# Metvoc2_0.net
KiCad netlist of a schematic drawn in EAGLE
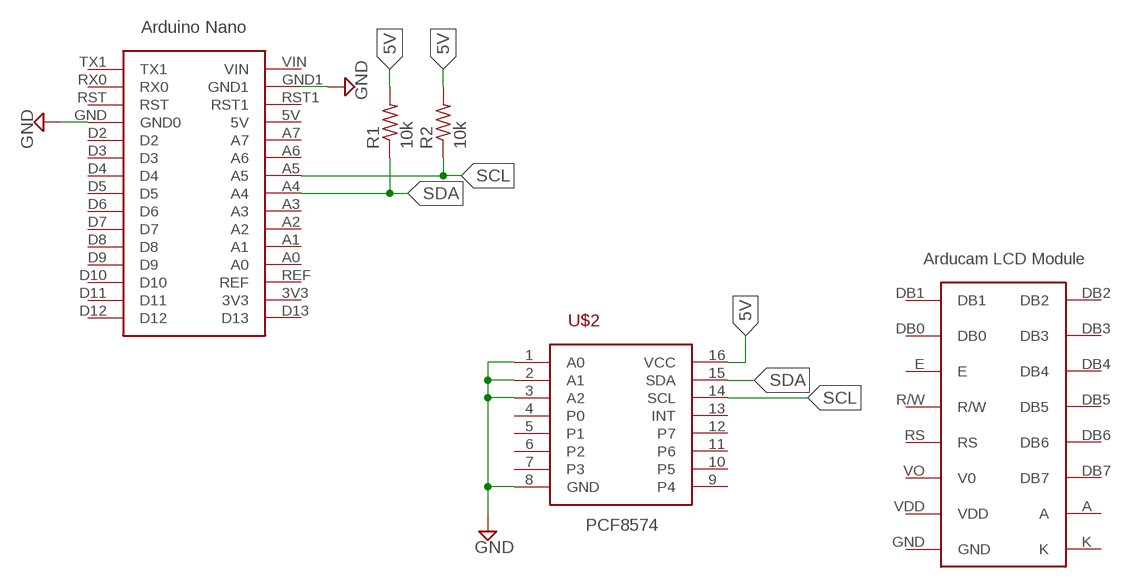
[diagram p0: schematic, sheet 1]

(export (version "E")
  (design (tool "Eeschema 10.0.6"))
  (components
    (comp (ref "R1")
      (value "10k")
      (footprint "eagle-import:M1206")
      (libsource (lib "eagle-import") (part "R-US_M1206"))
    )
    (comp (ref "R2")
      (value "10k")
      (footprint "eagle-import:M1206")
      (libsource (lib "eagle-import") (part "R-US_M1206"))
    )
    (comp (ref "U$1")
      (value "ARDUINO_NANO")
      (footprint "eagle-import:ARDUINONANO")
      (libsource (lib "eagle-import") (part "ARDUINO_NANO"))
    )
    (comp (ref "U$2")
      (value "PCF8574")
      (footprint "eagle-import:SO16")
      (libsource (lib "eagle-import") (part "PCF8574"))
    )
    (comp (ref "U$3")
      (value "LCDMODULE")
      (footprint "eagle-import:LCDSCREEN")
      (libsource (lib "eagle-import") (part "LCDMODULE"))
    )
  )
  (nets
    (net (code "1") (name "5V") (class "Default")
      (node (ref "R1") (pin "2") (pinfunction "2_2") (pintype "passive"))
      (node (ref "R2") (pin "2") (pinfunction "2_2") (pintype "passive"))
      (node (ref "U$2") (pin "16") (pinfunction "VCC_16") (pintype "bidirectional"))
    )
    (net (code "2") (name "GND") (class "Default")
      (node (ref "U$1") (pin "GND") (pinfunction "GND0_GND") (pintype "bidirectional"))
      (node (ref "U$1") (pin "GND1") (pinfunction "GND1_GND1") (pintype "bidirectional"))
      (node (ref "U$2") (pin "1") (pinfunction "A0_1") (pintype "bidirectional"))
      (node (ref "U$2") (pin "2") (pinfunction "A1_2") (pintype "bidirectional"))
      (node (ref "U$2") (pin "3") (pinfunction "A2_3") (pintype "bidirectional"))
      (node (ref "U$2") (pin "8") (pinfunction "GND_8") (pintype "bidirectional"))
    )
    (net (code "3") (name "SCL") (class "Default")
      (node (ref "R2") (pin "1") (pinfunction "1_1") (pintype "passive"))
      (node (ref "U$1") (pin "A5") (pinfunction "A5_A5") (pintype "bidirectional"))
      (node (ref "U$2") (pin "14") (pinfunction "SCL_14") (pintype "bidirectional"))
    )
    (net (code "4") (name "SDA") (class "Default")
      (node (ref "R1") (pin "1") (pinfunction "1_1") (pintype "passive"))
      (node (ref "U$1") (pin "A4") (pinfunction "A4_A4") (pintype "bidirectional"))
      (node (ref "U$2") (pin "15") (pinfunction "SDA_15") (pintype "bidirectional"))
    )
    (net (code "5") (name "unconnected-(U$1-Pad3V3)") (class "Default")
      (node (ref "U$1") (pin "3V3") (pinfunction "3V3_3V3") (pintype "bidirectional"))
    )
    (net (code "6") (name "unconnected-(U$1-Pad5V)") (class "Default")
      (node (ref "U$1") (pin "5V") (pinfunction "5V_5V") (pintype "bidirectional"))
    )
    (net (code "7") (name "unconnected-(U$1-PadA0)") (class "Default")
      (node (ref "U$1") (pin "A0") (pinfunction "A0_A0") (pintype "bidirectional"))
    )
    (net (code "8") (name "unconnected-(U$1-PadA1)") (class "Default")
      (node (ref "U$1") (pin "A1") (pinfunction "A1_A1") (pintype "bidirectional"))
    )
    (net (code "9") (name "unconnected-(U$1-PadA2)") (class "Default")
      (node (ref "U$1") (pin "A2") (pinfunction "A2_A2") (pintype "bidirectional"))
    )
    (net (code "10") (name "unconnected-(U$1-PadA3)") (class "Default")
      (node (ref "U$1") (pin "A3") (pinfunction "A3_A3") (pintype "bidirectional"))
    )
    (net (code "11") (name "unconnected-(U$1-PadA6)") (class "Default")
      (node (ref "U$1") (pin "A6") (pinfunction "A6_A6") (pintype "bidirectional"))
    )
    (net (code "12") (name "unconnected-(U$1-PadA7)") (class "Default")
      (node (ref "U$1") (pin "A7") (pinfunction "A7_A7") (pintype "bidirectional"))
    )
    (net (code "13") (name "unconnected-(U$1-PadD2)") (class "Default")
      (node (ref "U$1") (pin "D2") (pinfunction "D2_D2") (pintype "bidirectional"))
    )
    (net (code "14") (name "unconnected-(U$1-PadD3)") (class "Default")
      (node (ref "U$1") (pin "D3") (pinfunction "D3_D3") (pintype "bidirectional"))
    )
    (net (code "15") (name "unconnected-(U$1-PadD4)") (class "Default")
      (node (ref "U$1") (pin "D4") (pinfunction "D4_D4") (pintype "bidirectional"))
    )
    (net (code "16") (name "unconnected-(U$1-PadD5)") (class "Default")
      (node (ref "U$1") (pin "D5") (pinfunction "D5_D5") (pintype "bidirectional"))
    )
    (net (code "17") (name "unconnected-(U$1-PadD6)") (class "Default")
      (node (ref "U$1") (pin "D6") (pinfunction "D6_D6") (pintype "bidirectional"))
    )
    (net (code "18") (name "unconnected-(U$1-PadD7)") (class "Default")
      (node (ref "U$1") (pin "D7") (pinfunction "D7_D7") (pintype "bidirectional"))
    )
    (net (code "19") (name "unconnected-(U$1-PadD8)") (class "Default")
      (node (ref "U$1") (pin "D8") (pinfunction "D8_D8") (pintype "bidirectional"))
    )
    (net (code "20") (name "unconnected-(U$1-PadD9)") (class "Default")
      (node (ref "U$1") (pin "D9") (pinfunction "D9_D9") (pintype "bidirectional"))
    )
    (net (code "21") (name "unconnected-(U$1-PadD10)") (class "Default")
      (node (ref "U$1") (pin "D10") (pinfunction "D10_D10") (pintype "bidirectional"))
    )
    (net (code "22") (name "unconnected-(U$1-PadD11)") (class "Default")
      (node (ref "U$1") (pin "D11") (pinfunction "D11_D11") (pintype "bidirectional"))
    )
    (net (code "23") (name "unconnected-(U$1-PadD12)") (class "Default")
      (node (ref "U$1") (pin "D12") (pinfunction "D12_D12") (pintype "bidirectional"))
    )
    (net (code "24") (name "unconnected-(U$1-PadD13)") (class "Default")
      (node (ref "U$1") (pin "D13") (pinfunction "D13_D13") (pintype "bidirectional"))
    )
    (net (code "25") (name "unconnected-(U$1-PadREF)") (class "Default")
      (node (ref "U$1") (pin "REF") (pinfunction "REF_REF") (pintype "bidirectional"))
    )
    (net (code "26") (name "unconnected-(U$1-PadRST)") (class "Default")
      (node (ref "U$1") (pin "RST") (pinfunction "RST_RST") (pintype "bidirectional"))
    )
    (net (code "27") (name "unconnected-(U$1-PadRST1)") (class "Default")
      (node (ref "U$1") (pin "RST1") (pinfunction "RST1_RST1") (pintype "bidirectional"))
    )
    (net (code "28") (name "unconnected-(U$1-PadRX0)") (class "Default")
      (node (ref "U$1") (pin "RX0") (pinfunction "RX0_RX0") (pintype "bidirectional"))
    )
    (net (code "29") (name "unconnected-(U$1-PadTX1)") (class "Default")
      (node (ref "U$1") (pin "TX1") (pinfunction "TX1_TX1") (pintype "bidirectional"))
    )
    (net (code "30") (name "unconnected-(U$1-PadVIN)") (class "Default")
      (node (ref "U$1") (pin "VIN") (pinfunction "VIN_VIN") (pintype "bidirectional"))
    )
    (net (code "31") (name "unconnected-(U$2-INT-Pad13)") (class "Default")
      (node (ref "U$2") (pin "13") (pinfunction "INT_13") (pintype "bidirectional"))
    )
    (net (code "32") (name "unconnected-(U$2-P0-Pad4)") (class "Default")
      (node (ref "U$2") (pin "4") (pinfunction "P0_4") (pintype "bidirectional"))
    )
    (net (code "33") (name "unconnected-(U$2-P1-Pad5)") (class "Default")
      (node (ref "U$2") (pin "5") (pinfunction "P1_5") (pintype "bidirectional"))
    )
    (net (code "34") (name "unconnected-(U$2-P2-Pad6)") (class "Default")
      (node (ref "U$2") (pin "6") (pinfunction "P2_6") (pintype "bidirectional"))
    )
    (net (code "35") (name "unconnected-(U$2-P3-Pad7)") (class "Default")
      (node (ref "U$2") (pin "7") (pinfunction "P3_7") (pintype "bidirectional"))
    )
    (net (code "36") (name "unconnected-(U$2-P4-Pad9)") (class "Default")
      (node (ref "U$2") (pin "9") (pinfunction "P4_9") (pintype "bidirectional"))
    )
    (net (code "37") (name "unconnected-(U$2-P5-Pad10)") (class "Default")
      (node (ref "U$2") (pin "10") (pinfunction "P5_10") (pintype "bidirectional"))
    )
    (net (code "38") (name "unconnected-(U$2-P6-Pad11)") (class "Default")
      (node (ref "U$2") (pin "11") (pinfunction "P6_11") (pintype "bidirectional"))
    )
    (net (code "39") (name "unconnected-(U$2-P7-Pad12)") (class "Default")
      (node (ref "U$2") (pin "12") (pinfunction "P7_12") (pintype "bidirectional"))
    )
    (net (code "40") (name "unconnected-(U$3-PadA)") (class "Default")
      (node (ref "U$3") (pin "A") (pinfunction "A_A") (pintype "bidirectional"))
    )
    (net (code "41") (name "unconnected-(U$3-PadDB0)") (class "Default")
      (node (ref "U$3") (pin "DB0") (pinfunction "DB0_DB0") (pintype "bidirectional"))
    )
    (net (code "42") (name "unconnected-(U$3-PadDB1)") (class "Default")
      (node (ref "U$3") (pin "DB1") (pinfunction "DB1_DB1") (pintype "bidirectional"))
    )
    (net (code "43") (name "unconnected-(U$3-PadDB2)") (class "Default")
      (node (ref "U$3") (pin "DB2") (pinfunction "DB2_DB2") (pintype "bidirectional"))
    )
    (net (code "44") (name "unconnected-(U$3-PadDB3)") (class "Default")
      (node (ref "U$3") (pin "DB3") (pinfunction "DB3_DB3") (pintype "bidirectional"))
    )
    (net (code "45") (name "unconnected-(U$3-PadDB4)") (class "Default")
      (node (ref "U$3") (pin "DB4") (pinfunction "DB4_DB4") (pintype "bidirectional"))
    )
    (net (code "46") (name "unconnected-(U$3-PadDB5)") (class "Default")
      (node (ref "U$3") (pin "DB5") (pinfunction "DB5_DB5") (pintype "bidirectional"))
    )
    (net (code "47") (name "unconnected-(U$3-PadDB6)") (class "Default")
      (node (ref "U$3") (pin "DB6") (pinfunction "DB6_DB6") (pintype "bidirectional"))
    )
    (net (code "48") (name "unconnected-(U$3-PadDB7)") (class "Default")
      (node (ref "U$3") (pin "DB7") (pinfunction "DB7_DB7") (pintype "bidirectional"))
    )
    (net (code "49") (name "unconnected-(U$3-PadE)") (class "Default")
      (node (ref "U$3") (pin "E") (pinfunction "E_E") (pintype "bidirectional"))
    )
    (net (code "50") (name "unconnected-(U$3-PadGND)") (class "Default")
      (node (ref "U$3") (pin "GND") (pinfunction "GND_GND") (pintype "bidirectional"))
    )
    (net (code "51") (name "unconnected-(U$3-PadK)") (class "Default")
      (node (ref "U$3") (pin "K") (pinfunction "K_K") (pintype "bidirectional"))
    )
    (net (code "52") (name "unconnected-(U$3-PadRS)") (class "Default")
      (node (ref "U$3") (pin "RS") (pinfunction "RS_RS") (pintype "bidirectional"))
    )
    (net (code "53") (name "unconnected-(U$3-PadR{slash}W)") (class "Default")
      (node (ref "U$3") (pin "R/W") (pinfunction "R/W_R/W") (pintype "bidirectional"))
    )
    (net (code "54") (name "unconnected-(U$3-PadVDD)") (class "Default")
      (node (ref "U$3") (pin "VDD") (pinfunction "VDD_VDD") (pintype "bidirectional"))
    )
    (net (code "55") (name "unconnected-(U$3-V0-PadVO)") (class "Default")
      (node (ref "U$3") (pin "VO") (pinfunction "V0_VO") (pintype "bidirectional"))
    )
  )
)
